# ZED-F9P_GNSS_FeatherWing.net
KiCad netlist of a schematic drawn in EAGLE
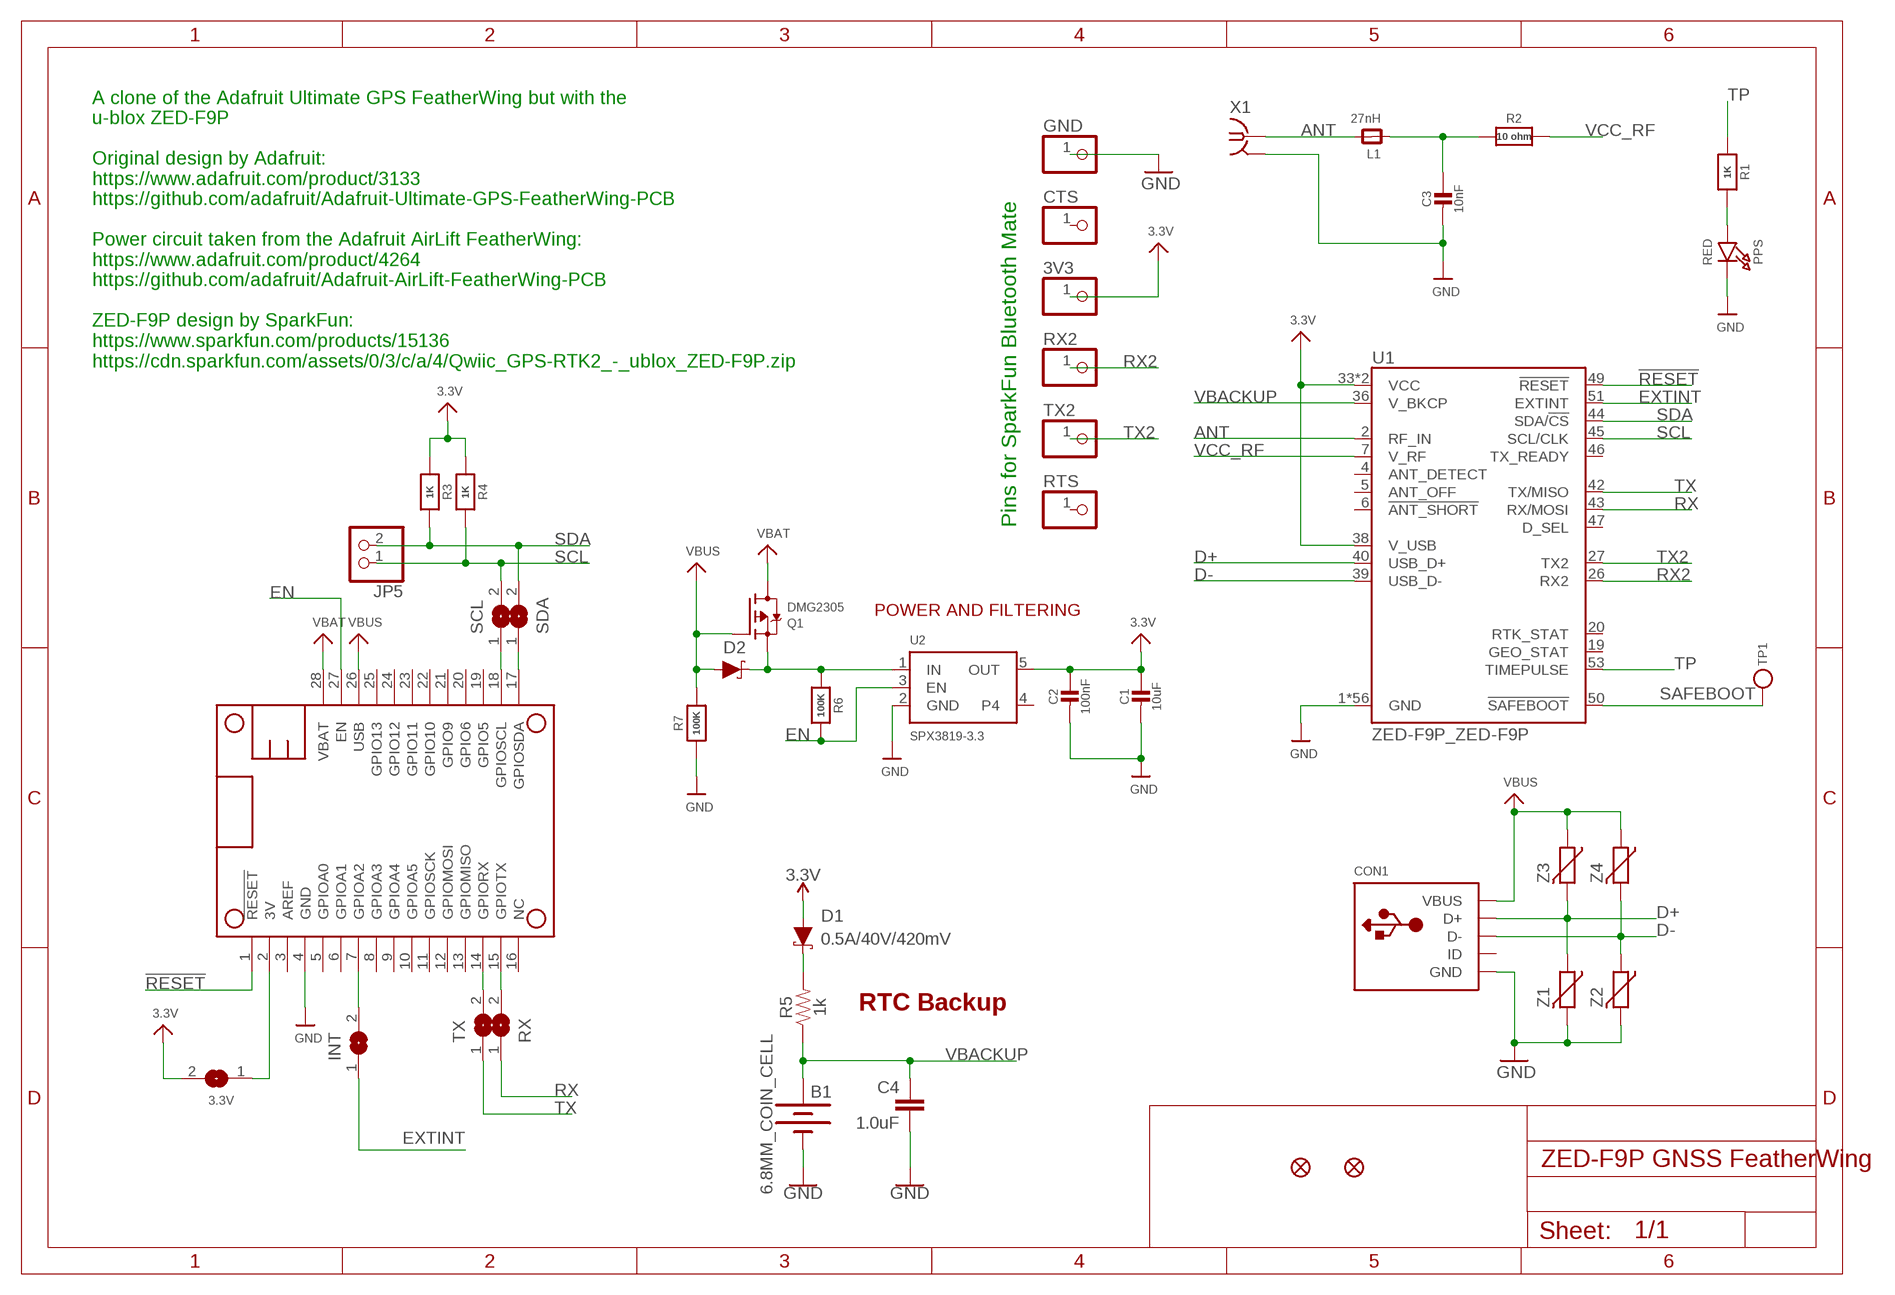
[diagram p0: schematic, sheet 1]

(export (version "E")
  (design (tool "Eeschema 10.0.6"))
  (components
    (comp (ref "3.3V")
      (value "SOLDERJUMPER")
      (footprint "eagle-import:SOLDERJUMPER_ARROW_NOPASTE")
      (libsource (lib "eagle-import") (part "SOLDERJUMPER"))
    )
    (comp (ref "3V3")
      (value "PINHD-1X1")
      (footprint "eagle-import:1X01")
      (libsource (lib "eagle-import") (part "PINHD-1X1"))
    )
    (comp (ref "B1")
      (value "6.8MM_COIN_CELL")
      (footprint "eagle-import:BATTCON-6.8MM")
      (libsource (lib "eagle-import") (part "BATTERY-6.8MM_SMD"))
    )
    (comp (ref "C1")
      (value "10uF")
      (footprint "eagle-import:0805-NO")
      (libsource (lib "eagle-import") (part "CAP_CERAMIC0805-NOOUTLINE"))
    )
    (comp (ref "C2")
      (value "100nF")
      (footprint "eagle-import:0805-NO")
      (libsource (lib "eagle-import") (part "CAP_CERAMIC0805-NOOUTLINE"))
    )
    (comp (ref "C3")
      (value "10nF")
      (footprint "eagle-import:0805-NO")
      (libsource (lib "eagle-import") (part "CAP_CERAMIC0805-NOOUTLINE"))
    )
    (comp (ref "C4")
      (value "1.0uF")
      (footprint "eagle-import:0603")
      (libsource (lib "eagle-import") (part "1.0UF-0603-16V-10%"))
    )
    (comp (ref "CON1")
      (value "MICROBUILDER_USBFCI_10103594_CORRECTED")
      (footprint "eagle-import:MICROBUILDER_FCI_10103594_CORRECTED")
      (libsource (lib "eagle-import") (part "MICROBUILDER_USBFCI_10103594_CORRECTED"))
    )
    (comp (ref "CTS")
      (value "PINHD-1X1")
      (footprint "eagle-import:1X01")
      (libsource (lib "eagle-import") (part "PINHD-1X1"))
    )
    (comp (ref "D1")
      (value "0.5A/40V/420mV")
      (footprint "eagle-import:SOD-323")
      (libsource (lib "eagle-import") (part "DIODE-SCHOTTKY-PMEG4005EJ"))
    )
    (comp (ref "D2")
      (value "0.5A/40V/420mV")
      (footprint "eagle-import:SOD-323")
      (libsource (lib "eagle-import") (part "DIODE-SCHOTTKY-PMEG4005EJ"))
    )
    (comp (ref "FID1")
      (value "FIDUCIAL\"\"")
      (footprint "eagle-import:FIDUCIAL_1MM")
      (libsource (lib "eagle-import") (part "FIDUCIAL{dblquote}{dblquote}"))
    )
    (comp (ref "FID2")
      (value "FIDUCIAL\"\"")
      (footprint "eagle-import:FIDUCIAL_1MM")
      (libsource (lib "eagle-import") (part "FIDUCIAL{dblquote}{dblquote}"))
    )
    (comp (ref "GND")
      (value "PINHD-1X1")
      (footprint "eagle-import:1X01")
      (libsource (lib "eagle-import") (part "PINHD-1X1"))
    )
    (comp (ref "INT")
      (value "SOLDERJUMPERCLOSED")
      (footprint "eagle-import:SOLDERJUMPER_CLOSEDWIRE")
      (libsource (lib "eagle-import") (part "SOLDERJUMPERCLOSED"))
    )
    (comp (ref "JP5")
      (value "HEADER-1X2ROUND")
      (footprint "eagle-import:1X02_ROUND")
      (libsource (lib "eagle-import") (part "HEADER-1X2ROUND"))
    )
    (comp (ref "L1")
      (value "27nH")
      (footprint "eagle-import:0805-NO")
      (libsource (lib "eagle-import") (part "FERRITE-0805NO"))
    )
    (comp (ref "MS1")
      (value "MICROBUILDER_FEATHERWINGMICROBUILDER_FEATHERWING_HOLES")
      (footprint "eagle-import:MICROBUILDER_FEATHERWING_HOLES")
      (libsource (lib "eagle-import") (part "MICROBUILDER_FEATHERWINGMICROBUILDER_FEATHERWING_HOLES"))
    )
    (comp (ref "PPS")
      (value "RED")
      (footprint "eagle-import:CHIPLED_0805_NOOUTLINE")
      (libsource (lib "eagle-import") (part "LED0805_NOOUTLINE"))
    )
    (comp (ref "Q1")
      (value "DMG2305")
      (footprint "eagle-import:SOT23-R")
      (libsource (lib "eagle-import") (part "MOSFET-P"))
    )
    (comp (ref "R1")
      (value "1K")
      (footprint "eagle-import:0603-NO")
      (libsource (lib "eagle-import") (part "RESISTOR_0603_NOOUT"))
    )
    (comp (ref "R2")
      (value "10 ohm")
      (footprint "eagle-import:0805-NO")
      (libsource (lib "eagle-import") (part "RESISTOR0805_NOOUTLINE"))
    )
    (comp (ref "R3")
      (value "1K")
      (footprint "eagle-import:0603-NO")
      (libsource (lib "eagle-import") (part "RESISTOR_0603_NOOUT"))
    )
    (comp (ref "R4")
      (value "1K")
      (footprint "eagle-import:0603-NO")
      (libsource (lib "eagle-import") (part "RESISTOR_0603_NOOUT"))
    )
    (comp (ref "R5")
      (value "1k")
      (footprint "eagle-import:0603")
      (libsource (lib "eagle-import") (part "1KOHM-0603-1/10W-1%"))
    )
    (comp (ref "R6")
      (value "100K")
      (footprint "eagle-import:0603-NO")
      (libsource (lib "eagle-import") (part "RESISTOR_0603_NOOUT"))
    )
    (comp (ref "R7")
      (value "100K")
      (footprint "eagle-import:0603-NO")
      (libsource (lib "eagle-import") (part "RESISTOR_0603_NOOUT"))
    )
    (comp (ref "RTS")
      (value "PINHD-1X1")
      (footprint "eagle-import:1X01")
      (libsource (lib "eagle-import") (part "PINHD-1X1"))
    )
    (comp (ref "RX")
      (value "SOLDERJUMPERCLOSED")
      (footprint "eagle-import:SOLDERJUMPER_CLOSEDWIRE")
      (libsource (lib "eagle-import") (part "SOLDERJUMPERCLOSED"))
    )
    (comp (ref "RX2")
      (value "PINHD-1X1")
      (footprint "eagle-import:1X01")
      (libsource (lib "eagle-import") (part "PINHD-1X1"))
    )
    (comp (ref "SCL")
      (value "SOLDERJUMPERCLOSED")
      (footprint "eagle-import:SOLDERJUMPER_CLOSEDWIRE")
      (libsource (lib "eagle-import") (part "SOLDERJUMPERCLOSED"))
    )
    (comp (ref "SDA")
      (value "SOLDERJUMPERCLOSED")
      (footprint "eagle-import:SOLDERJUMPER_CLOSEDWIRE")
      (libsource (lib "eagle-import") (part "SOLDERJUMPERCLOSED"))
    )
    (comp (ref "TP1")
      (value "TESTPOINTROUND1.5MM")
      (footprint "eagle-import:TESTPOINT_ROUND_1.5MM")
      (libsource (lib "eagle-import") (part "TESTPOINTROUND1.5MM"))
    )
    (comp (ref "TX")
      (value "SOLDERJUMPERCLOSED")
      (footprint "eagle-import:SOLDERJUMPER_CLOSEDWIRE")
      (libsource (lib "eagle-import") (part "SOLDERJUMPERCLOSED"))
    )
    (comp (ref "TX2")
      (value "PINHD-1X1")
      (footprint "eagle-import:1X01")
      (libsource (lib "eagle-import") (part "PINHD-1X1"))
    )
    (comp (ref "U1")
      (value "ZED-F9P_ZED-F9P")
      (footprint "eagle-import:ZED-F9P_ZED-F9P")
      (libsource (lib "eagle-import") (part "ZED-F9P_ZED-F9P"))
    )
    (comp (ref "U2")
      (value "SPX3819-3.3")
      (footprint "eagle-import:SOT23-5")
      (libsource (lib "eagle-import") (part "VREG_SOT23-5"))
    )
    (comp (ref "X1")
      (value "SMA-142-0711-821/826")
      (footprint "eagle-import:J502-ND-142-0711-821_826")
      (fields (field (name "MF") "JOHNSON COMPONENTS") (field (name "MPN") "142-0711-821"))
      (libsource (lib "eagle-import") (part "SMA-142-0711-821/826"))
    )
    (comp (ref "Z1")
      (value "CG0603MLC-05E")
      (footprint "eagle-import:CT_CN0603")
      (fields (field (name "PART_NUMBER") "BRNCG0603MLC-05E"))
      (libsource (lib "eagle-import") (part "0010_BRNCG0603MLC-05E"))
    )
    (comp (ref "Z2")
      (value "CG0603MLC-05E")
      (footprint "eagle-import:CT_CN0603")
      (fields (field (name "PART_NUMBER") "BRNCG0603MLC-05E"))
      (libsource (lib "eagle-import") (part "0010_BRNCG0603MLC-05E"))
    )
    (comp (ref "Z3")
      (value "CG0603MLC-05E")
      (footprint "eagle-import:CT_CN0603")
      (fields (field (name "PART_NUMBER") "BRNCG0603MLC-05E"))
      (libsource (lib "eagle-import") (part "0010_BRNCG0603MLC-05E"))
    )
    (comp (ref "Z4")
      (value "CG0603MLC-05E")
      (footprint "eagle-import:CT_CN0603")
      (fields (field (name "PART_NUMBER") "BRNCG0603MLC-05E"))
      (libsource (lib "eagle-import") (part "0010_BRNCG0603MLC-05E"))
    )
  )
  (nets
    (net (code "1") (name "/ANT") (class "Default")
      (node (ref "L1") (pin "2") (pinfunction "P$2_2") (pintype "passive"))
      (node (ref "U1") (pin "2") (pinfunction "RF_IN_2") (pintype "bidirectional"))
      (node (ref "X1") (pin "1") (pinfunction "1_1") (pintype "passive"))
    )
    (net (code "2") (name "/D+") (class "Default")
      (node (ref "CON1") (pin "D+") (pinfunction "D+_D+") (pintype "bidirectional"))
      (node (ref "U1") (pin "40") (pinfunction "USB_D+_40") (pintype "bidirectional"))
      (node (ref "Z1") (pin "1") (pinfunction "1_1") (pintype "passive"))
      (node (ref "Z3") (pin "2") (pinfunction "2_2") (pintype "passive"))
    )
    (net (code "3") (name "/D-") (class "Default")
      (node (ref "CON1") (pin "D-") (pinfunction "D-_D-") (pintype "bidirectional"))
      (node (ref "U1") (pin "39") (pinfunction "USB_D-_39") (pintype "bidirectional"))
      (node (ref "Z2") (pin "1") (pinfunction "1_1") (pintype "passive"))
      (node (ref "Z4") (pin "2") (pinfunction "2_2") (pintype "passive"))
    )
    (net (code "4") (name "/EN") (class "Default")
      (node (ref "MS1") (pin "27") (pinfunction "EN_27") (pintype "passive"))
      (node (ref "R6") (pin "2") (pinfunction "2_2") (pintype "passive"))
      (node (ref "U2") (pin "3") (pinfunction "EN_3") (pintype "input"))
    )
    (net (code "5") (name "/EXTINT") (class "Default")
      (node (ref "INT") (pin "1") (pinfunction "1_1") (pintype "passive"))
      (node (ref "U1") (pin "51") (pinfunction "EXTINT_51") (pintype "bidirectional"))
    )
    (net (code "6") (name "/RX") (class "Default")
      (node (ref "RX") (pin "1") (pinfunction "1_1") (pintype "passive"))
      (node (ref "U1") (pin "43") (pinfunction "RX/MOSI_43") (pintype "bidirectional"))
    )
    (net (code "7") (name "/RX2") (class "Default")
      (node (ref "RX2") (pin "1") (pinfunction "1_1") (pintype "passive"))
      (node (ref "U1") (pin "26") (pinfunction "RX2_26") (pintype "bidirectional"))
    )
    (net (code "8") (name "/SAFEBOOT") (class "Default")
      (node (ref "TP1") (pin "P$1") (pinfunction "P$1_P$1") (pintype "bidirectional"))
      (node (ref "U1") (pin "50") (pinfunction "~{SAFEBOOT}_50") (pintype "bidirectional"))
    )
    (net (code "9") (name "/SCL") (class "Default")
      (node (ref "JP5") (pin "1") (pinfunction "1_1") (pintype "passive"))
      (node (ref "R4") (pin "2") (pinfunction "2_2") (pintype "passive"))
      (node (ref "SCL") (pin "2") (pinfunction "2_2") (pintype "passive"))
      (node (ref "U1") (pin "45") (pinfunction "SCL/CLK_45") (pintype "bidirectional"))
    )
    (net (code "10") (name "/SDA") (class "Default")
      (node (ref "JP5") (pin "2") (pinfunction "2_2") (pintype "passive"))
      (node (ref "R3") (pin "2") (pinfunction "2_2") (pintype "passive"))
      (node (ref "SDA") (pin "2") (pinfunction "2_2") (pintype "passive"))
      (node (ref "U1") (pin "44") (pinfunction "SDA/~{CS}_44") (pintype "bidirectional"))
    )
    (net (code "11") (name "/TP") (class "Default")
      (node (ref "R1") (pin "1") (pinfunction "1_1") (pintype "passive"))
      (node (ref "U1") (pin "53") (pinfunction "TIMEPULSE_53") (pintype "bidirectional"))
    )
    (net (code "12") (name "/TX") (class "Default")
      (node (ref "TX") (pin "1") (pinfunction "1_1") (pintype "passive"))
      (node (ref "U1") (pin "42") (pinfunction "TX/MISO_42") (pintype "bidirectional"))
    )
    (net (code "13") (name "/TX2") (class "Default")
      (node (ref "TX2") (pin "1") (pinfunction "1_1") (pintype "passive"))
      (node (ref "U1") (pin "27") (pinfunction "TX2_27") (pintype "bidirectional"))
    )
    (net (code "14") (name "/VBACKUP") (class "Default")
      (node (ref "B1") (pin "+") (pinfunction "+_+") (pintype "power_in"))
      (node (ref "C4") (pin "1") (pinfunction "1_1") (pintype "passive"))
      (node (ref "R5") (pin "1") (pinfunction "1_1") (pintype "passive"))
      (node (ref "U1") (pin "36") (pinfunction "V_BKCP_36") (pintype "bidirectional"))
    )
    (net (code "15") (name "/VCC_RF") (class "Default")
      (node (ref "R2") (pin "2") (pinfunction "2_2") (pintype "passive"))
      (node (ref "U1") (pin "7") (pinfunction "V_RF_7") (pintype "bidirectional"))
    )
    (net (code "16") (name "/~{RESET}") (class "Default")
      (node (ref "MS1") (pin "1") (pinfunction "~{RESET}_1") (pintype "input"))
      (node (ref "U1") (pin "49") (pinfunction "~{RESET}_49") (pintype "bidirectional"))
    )
    (net (code "17") (name "3.3V") (class "Default")
      (node (ref "3.3V") (pin "2") (pinfunction "2_2") (pintype "passive"))
      (node (ref "3V3") (pin "1") (pinfunction "1_1") (pintype "passive"))
      (node (ref "C1") (pin "1") (pinfunction "1_1") (pintype "passive"))
      (node (ref "C2") (pin "1") (pinfunction "1_1") (pintype "passive"))
      (node (ref "D1") (pin "A") (pinfunction "A_A") (pintype "passive"))
      (node (ref "R3") (pin "1") (pinfunction "1_1") (pintype "passive"))
      (node (ref "R4") (pin "1") (pinfunction "1_1") (pintype "passive"))
      (node (ref "U1") (pin "33") (pinfunction "VCC_33") (pintype "bidirectional"))
      (node (ref "U1") (pin "34") (pinfunction "VCC_34") (pintype "bidirectional"))
      (node (ref "U1") (pin "38") (pinfunction "V_USB_38") (pintype "bidirectional"))
      (node (ref "U2") (pin "5") (pinfunction "OUT_5") (pintype "power_in"))
    )
    (net (code "18") (name "GND") (class "Default")
      (node (ref "B1") (pin "-") (pinfunction "-_-") (pintype "power_in"))
      (node (ref "C1") (pin "2") (pinfunction "2_2") (pintype "passive"))
      (node (ref "C2") (pin "2") (pinfunction "2_2") (pintype "passive"))
      (node (ref "C3") (pin "2") (pinfunction "2_2") (pintype "passive"))
      (node (ref "C4") (pin "2") (pinfunction "2_2") (pintype "passive"))
      (node (ref "CON1") (pin "BASE@1") (pinfunction "GND_BASE@1") (pintype "power_in"))
      (node (ref "CON1") (pin "BASE@2") (pinfunction "GND_BASE@2") (pintype "power_in"))
      (node (ref "CON1") (pin "GND") (pinfunction "GND_GND") (pintype "power_in"))
      (node (ref "CON1") (pin "SPRT@1") (pinfunction "GND_SPRT@1") (pintype "power_in"))
      (node (ref "CON1") (pin "SPRT@2") (pinfunction "GND_SPRT@2") (pintype "power_in"))
      (node (ref "CON1") (pin "SPRT@3") (pinfunction "GND_SPRT@3") (pintype "power_in"))
      (node (ref "CON1") (pin "SPRT@4") (pinfunction "GND_SPRT@4") (pintype "power_in"))
      (node (ref "GND") (pin "1") (pinfunction "1_1") (pintype "passive"))
      (node (ref "MS1") (pin "4") (pinfunction "GND_4") (pintype "power_in"))
      (node (ref "PPS") (pin "C") (pinfunction "C_C") (pintype "passive"))
      (node (ref "R7") (pin "1") (pinfunction "1_1") (pintype "passive"))
      (node (ref "U1") (pin "1") (pinfunction "GND_1") (pintype "bidirectional"))
      (node (ref "U1") (pin "100") (pinfunction "GND_100") (pintype "bidirectional"))
      (node (ref "U1") (pin "101") (pinfunction "GND_101") (pintype "bidirectional"))
      (node (ref "U1") (pin "102") (pinfunction "GND_102") (pintype "bidirectional"))
      (node (ref "U1") (pin "12") (pinfunction "GND_12") (pintype "bidirectional"))
      (node (ref "U1") (pin "14") (pinfunction "GND_14") (pintype "bidirectional"))
      (node (ref "U1") (pin "3") (pinfunction "GND_3") (pintype "bidirectional"))
      (node (ref "U1") (pin "32") (pinfunction "GND_32") (pintype "bidirectional"))
      (node (ref "U1") (pin "37") (pinfunction "GND_37") (pintype "bidirectional"))
      (node (ref "U1") (pin "41") (pinfunction "GND_41") (pintype "bidirectional"))
      (node (ref "U1") (pin "48") (pinfunction "GND_48") (pintype "bidirectional"))
      (node (ref "U1") (pin "55") (pinfunction "GND_55") (pintype "bidirectional"))
      (node (ref "U1") (pin "56") (pinfunction "GND_56") (pintype "bidirectional"))
      (node (ref "U1") (pin "57") (pinfunction "GND_57") (pintype "bidirectional"))
      (node (ref "U1") (pin "58") (pinfunction "GND_58") (pintype "bidirectional"))
      (node (ref "U1") (pin "59") (pinfunction "GND_59") (pintype "bidirectional"))
      (node (ref "U1") (pin "60") (pinfunction "GND_60") (pintype "bidirectional"))
      (node (ref "U1") (pin "61") (pinfunction "GND_61") (pintype "bidirectional"))
      (node (ref "U1") (pin "62") (pinfunction "GND_62") (pintype "bidirectional"))
      (node (ref "U1") (pin "63") (pinfunction "GND_63") (pintype "bidirectional"))
      (node (ref "U1") (pin "64") (pinfunction "GND_64") (pintype "bidirectional"))
      (node (ref "U1") (pin "65") (pinfunction "GND_65") (pintype "bidirectional"))
      (node (ref "U1") (pin "66") (pinfunction "GND_66") (pintype "bidirectional"))
      (node (ref "U1") (pin "67") (pinfunction "GND_67") (pintype "bidirectional"))
      (node (ref "U1") (pin "68") (pinfunction "GND_68") (pintype "bidirectional"))
      (node (ref "U1") (pin "69") (pinfunction "GND_69") (pintype "bidirectional"))
      (node (ref "U1") (pin "70") (pinfunction "GND_70") (pintype "bidirectional"))
      (node (ref "U1") (pin "71") (pinfunction "GND_71") (pintype "bidirectional"))
      (node (ref "U1") (pin "72") (pinfunction "GND_72") (pintype "bidirectional"))
      (node (ref "U1") (pin "73") (pinfunction "GND_73") (pintype "bidirectional"))
      (node (ref "U1") (pin "74") (pinfunction "GND_74") (pintype "bidirectional"))
      (node (ref "U1") (pin "75") (pinfunction "GND_75") (pintype "bidirectional"))
      (node (ref "U1") (pin "76") (pinfunction "GND_76") (pintype "bidirectional"))
      (node (ref "U1") (pin "77") (pinfunction "GND_77") (pintype "bidirectional"))
      (node (ref "U1") (pin "78") (pinfunction "GND_78") (pintype "bidirectional"))
      (node (ref "U1") (pin "79") (pinfunction "GND_79") (pintype "bidirectional"))
      (node (ref "U1") (pin "80") (pinfunction "GND_80") (pintype "bidirectional"))
      (node (ref "U1") (pin "81") (pinfunction "GND_81") (pintype "bidirectional"))
      (node (ref "U1") (pin "82") (pinfunction "GND_82") (pintype "bidirectional"))
      (node (ref "U1") (pin "83") (pinfunction "GND_83") (pintype "bidirectional"))
      (node (ref "U1") (pin "84") (pinfunction "GND_84") (pintype "bidirectional"))
      (node (ref "U1") (pin "85") (pinfunction "GND_85") (pintype "bidirectional"))
      (node (ref "U1") (pin "86") (pinfunction "GND_86") (pintype "bidirectional"))
      (node (ref "U1") (pin "87") (pinfunction "GND_87") (pintype "bidirectional"))
      (node (ref "U1") (pin "88") (pinfunction "GND_88") (pintype "bidirectional"))
      (node (ref "U1") (pin "89") (pinfunction "GND_89") (pintype "bidirectional"))
      (node (ref "U1") (pin "90") (pinfunction "GND_90") (pintype "bidirectional"))
      (node (ref "U1") (pin "91") (pinfunction "GND_91") (pintype "bidirectional"))
      (node (ref "U1") (pin "92") (pinfunction "GND_92") (pintype "bidirectional"))
      (node (ref "U1") (pin "93") (pinfunction "GND_93") (pintype "bidirectional"))
      (node (ref "U1") (pin "94") (pinfunction "GND_94") (pintype "bidirectional"))
      (node (ref "U1") (pin "95") (pinfunction "GND_95") (pintype "bidirectional"))
      (node (ref "U1") (pin "96") (pinfunction "GND_96") (pintype "bidirectional"))
      (node (ref "U1") (pin "97") (pinfunction "GND_97") (pintype "bidirectional"))
      (node (ref "U1") (pin "98") (pinfunction "GND_98") (pintype "bidirectional"))
      (node (ref "U1") (pin "99") (pinfunction "GND_99") (pintype "bidirectional"))
      (node (ref "U2") (pin "2") (pinfunction "GND_2") (pintype "power_in"))
      (node (ref "X1") (pin "G@1") (pinfunction "2_G@1") (pintype "passive"))
      (node (ref "X1") (pin "G@2") (pinfunction "2_G@2") (pintype "passive"))
      (node (ref "X1") (pin "G@3") (pinfunction "2_G@3") (pintype "passive"))
      (node (ref "X1") (pin "G@4") (pinfunction "2_G@4") (pintype "passive"))
      (node (ref "Z1") (pin "2") (pinfunction "2_2") (pintype "passive"))
      (node (ref "Z2") (pin "2") (pinfunction "2_2") (pintype "passive"))
    )
    (net (code "19") (name "Net-(D1-PadC)") (class "Default")
      (node (ref "D1") (pin "C") (pinfunction "C_C") (pintype "passive"))
      (node (ref "R5") (pin "2") (pinfunction "2_2") (pintype "passive"))
    )
    (net (code "20") (name "Net-(L1-P$1)") (class "Default")
      (node (ref "C3") (pin "1") (pinfunction "1_1") (pintype "passive"))
      (node (ref "L1") (pin "1") (pinfunction "P$1_1") (pintype "passive"))
      (node (ref "R2") (pin "1") (pinfunction "1_1") (pintype "passive"))
    )
    (net (code "21") (name "Net-(MS1-3V)") (class "Default")
      (node (ref "3.3V") (pin "1") (pinfunction "1_1") (pintype "passive"))
      (node (ref "MS1") (pin "2") (pinfunction "3V_2") (pintype "power_in"))
    )
    (net (code "22") (name "Net-(MS1-GPIOA2)") (class "Default")
      (node (ref "INT") (pin "2") (pinfunction "2_2") (pintype "passive"))
      (node (ref "MS1") (pin "7") (pinfunction "GPIOA2_7") (pintype "bidirectional"))
    )
    (net (code "23") (name "Net-(MS1-GPIORX)") (class "Default")
      (node (ref "MS1") (pin "14") (pinfunction "GPIORX_14") (pintype "bidirectional"))
      (node (ref "TX") (pin "2") (pinfunction "2_2") (pintype "passive"))
    )
    (net (code "24") (name "Net-(MS1-GPIOSCL)") (class "Default")
      (node (ref "MS1") (pin "18") (pinfunction "GPIOSCL_18") (pintype "bidirectional"))
      (node (ref "SCL") (pin "1") (pinfunction "1_1") (pintype "passive"))
    )
    (net (code "25") (name "Net-(MS1-GPIOSDA)") (class "Default")
      (node (ref "MS1") (pin "17") (pinfunction "GPIOSDA_17") (pintype "bidirectional"))
      (node (ref "SDA") (pin "1") (pinfunction "1_1") (pintype "passive"))
    )
    (net (code "26") (name "Net-(MS1-GPIOTX)") (class "Default")
      (node (ref "MS1") (pin "15") (pinfunction "GPIOTX_15") (pintype "bidirectional"))
      (node (ref "RX") (pin "2") (pinfunction "2_2") (pintype "passive"))
    )
    (net (code "27") (name "Net-(PPS-PadA)") (class "Default")
      (node (ref "PPS") (pin "A") (pinfunction "A_A") (pintype "passive"))
      (node (ref "R1") (pin "2") (pinfunction "2_2") (pintype "passive"))
    )
    (net (code "28") (name "Net-(Q1-S)") (class "Default")
      (node (ref "D2") (pin "C") (pinfunction "C_C") (pintype "passive"))
      (node (ref "Q1") (pin "2") (pinfunction "S_2") (pintype "passive"))
      (node (ref "R6") (pin "1") (pinfunction "1_1") (pintype "passive"))
      (node (ref "U2") (pin "1") (pinfunction "IN_1") (pintype "power_in"))
    )
    (net (code "29") (name "VBAT") (class "Default")
      (node (ref "MS1") (pin "28") (pinfunction "VBAT_28") (pintype "power_in"))
      (node (ref "Q1") (pin "3") (pinfunction "D_3") (pintype "passive"))
    )
    (net (code "30") (name "VBUS") (class "Default")
      (node (ref "CON1") (pin "VBUS") (pinfunction "VBUS_VBUS") (pintype "power_in"))
      (node (ref "D2") (pin "A") (pinfunction "A_A") (pintype "passive"))
      (node (ref "MS1") (pin "26") (pinfunction "USB_26") (pintype "power_in"))
      (node (ref "Q1") (pin "1") (pinfunction "G_1") (pintype "passive"))
      (node (ref "R7") (pin "2") (pinfunction "2_2") (pintype "passive"))
      (node (ref "Z3") (pin "1") (pinfunction "1_1") (pintype "passive"))
      (node (ref "Z4") (pin "1") (pinfunction "1_1") (pintype "passive"))
    )
    (net (code "31") (name "unconnected-(CON1-PadID)") (class "Default")
      (node (ref "CON1") (pin "ID") (pinfunction "ID_ID") (pintype "bidirectional"))
    )
    (net (code "32") (name "unconnected-(CTS-Pad1)") (class "Default")
      (node (ref "CTS") (pin "1") (pinfunction "1_1") (pintype "passive"))
    )
    (net (code "33") (name "unconnected-(MS1-AREF-Pad3)") (class "Default")
      (node (ref "MS1") (pin "3") (pinfunction "AREF_3") (pintype "passive"))
    )
    (net (code "34") (name "unconnected-(MS1-GPIO5-Pad19)") (class "Default")
      (node (ref "MS1") (pin "19") (pinfunction "GPIO5_19") (pintype "bidirectional"))
    )
    (net (code "35") (name "unconnected-(MS1-GPIO6-Pad20)") (class "Default")
      (node (ref "MS1") (pin "20") (pinfunction "GPIO6_20") (pintype "bidirectional"))
    )
    (net (code "36") (name "unconnected-(MS1-GPIO9-Pad21)") (class "Default")
      (node (ref "MS1") (pin "21") (pinfunction "GPIO9_21") (pintype "bidirectional"))
    )
    (net (code "37") (name "unconnected-(MS1-GPIO10-Pad22)") (class "Default")
      (node (ref "MS1") (pin "22") (pinfunction "GPIO10_22") (pintype "bidirectional"))
    )
    (net (code "38") (name "unconnected-(MS1-GPIO11-Pad23)") (class "Default")
      (node (ref "MS1") (pin "23") (pinfunction "GPIO11_23") (pintype "bidirectional"))
    )
    (net (code "39") (name "unconnected-(MS1-GPIO12-Pad24)") (class "Default")
      (node (ref "MS1") (pin "24") (pinfunction "GPIO12_24") (pintype "bidirectional"))
    )
    (net (code "40") (name "unconnected-(MS1-GPIO13-Pad25)") (class "Default")
      (node (ref "MS1") (pin "25") (pinfunction "GPIO13_25") (pintype "bidirectional"))
    )
    (net (code "41") (name "unconnected-(MS1-GPIOA0-Pad5)") (class "Default")
      (node (ref "MS1") (pin "5") (pinfunction "GPIOA0_5") (pintype "bidirectional"))
    )
    (net (code "42") (name "unconnected-(MS1-GPIOA1-Pad6)") (class "Default")
      (node (ref "MS1") (pin "6") (pinfunction "GPIOA1_6") (pintype "bidirectional"))
    )
    (net (code "43") (name "unconnected-(MS1-GPIOA3-Pad8)") (class "Default")
      (node (ref "MS1") (pin "8") (pinfunction "GPIOA3_8") (pintype "bidirectional"))
    )
    (net (code "44") (name "unconnected-(MS1-GPIOA4-Pad9)") (class "Default")
      (node (ref "MS1") (pin "9") (pinfunction "GPIOA4_9") (pintype "bidirectional"))
    )
    (net (code "45") (name "unconnected-(MS1-GPIOA5-Pad10)") (class "Default")
      (node (ref "MS1") (pin "10") (pinfunction "GPIOA5_10") (pintype "bidirectional"))
    )
    (net (code "46") (name "unconnected-(MS1-GPIOMISO-Pad13)") (class "Default")
      (node (ref "MS1") (pin "13") (pinfunction "GPIOMISO_13") (pintype "bidirectional"))
    )
    (net (code "47") (name "unconnected-(MS1-GPIOMOSI-Pad12)") (class "Default")
      (node (ref "MS1") (pin "12") (pinfunction "GPIOMOSI_12") (pintype "bidirectional"))
    )
    (net (code "48") (name "unconnected-(MS1-GPIOSCK-Pad11)") (class "Default")
      (node (ref "MS1") (pin "11") (pinfunction "GPIOSCK_11") (pintype "bidirectional"))
    )
    (net (code "49") (name "unconnected-(MS1-NC-Pad16)") (class "Default")
      (node (ref "MS1") (pin "16") (pinfunction "NC_16") (pintype "passive"))
    )
    (net (code "50") (name "unconnected-(RTS-Pad1)") (class "Default")
      (node (ref "RTS") (pin "1") (pinfunction "1_1") (pintype "passive"))
    )
    (net (code "51") (name "unconnected-(U1-ANT_DETECT-Pad4)") (class "Default")
      (node (ref "U1") (pin "4") (pinfunction "ANT_DETECT_4") (pintype "bidirectional"))
    )
    (net (code "52") (name "unconnected-(U1-ANT_OFF-Pad5)") (class "Default")
      (node (ref "U1") (pin "5") (pinfunction "ANT_OFF_5") (pintype "bidirectional"))
    )
    (net (code "53") (name "unconnected-(U1-D_SEL-Pad47)") (class "Default")
      (node (ref "U1") (pin "47") (pinfunction "D_SEL_47") (pintype "bidirectional"))
    )
    (net (code "54") (name "unconnected-(U1-GEO_STAT-Pad19)") (class "Default")
      (node (ref "U1") (pin "19") (pinfunction "GEO_STAT_19") (pintype "bidirectional"))
    )
    (net (code "55") (name "unconnected-(U1-RTK_STAT-Pad20)") (class "Default")
      (node (ref "U1") (pin "20") (pinfunction "RTK_STAT_20") (pintype "bidirectional"))
    )
    (net (code "56") (name "unconnected-(U1-TX_READY-Pad46)") (class "Default")
      (node (ref "U1") (pin "46") (pinfunction "TX_READY_46") (pintype "bidirectional"))
    )
    (net (code "57") (name "unconnected-(U1-~{ANT_SHORT}-Pad6)") (class "Default")
      (node (ref "U1") (pin "6") (pinfunction "~{ANT_SHORT}_6") (pintype "bidirectional"))
    )
    (net (code "58") (name "unconnected-(U2-P4-Pad4)") (class "Default")
      (node (ref "U2") (pin "4") (pinfunction "P4_4") (pintype "bidirectional"))
    )
  )
)
